# 28vdcEagle.net
KiCad netlist of a schematic drawn in EAGLE
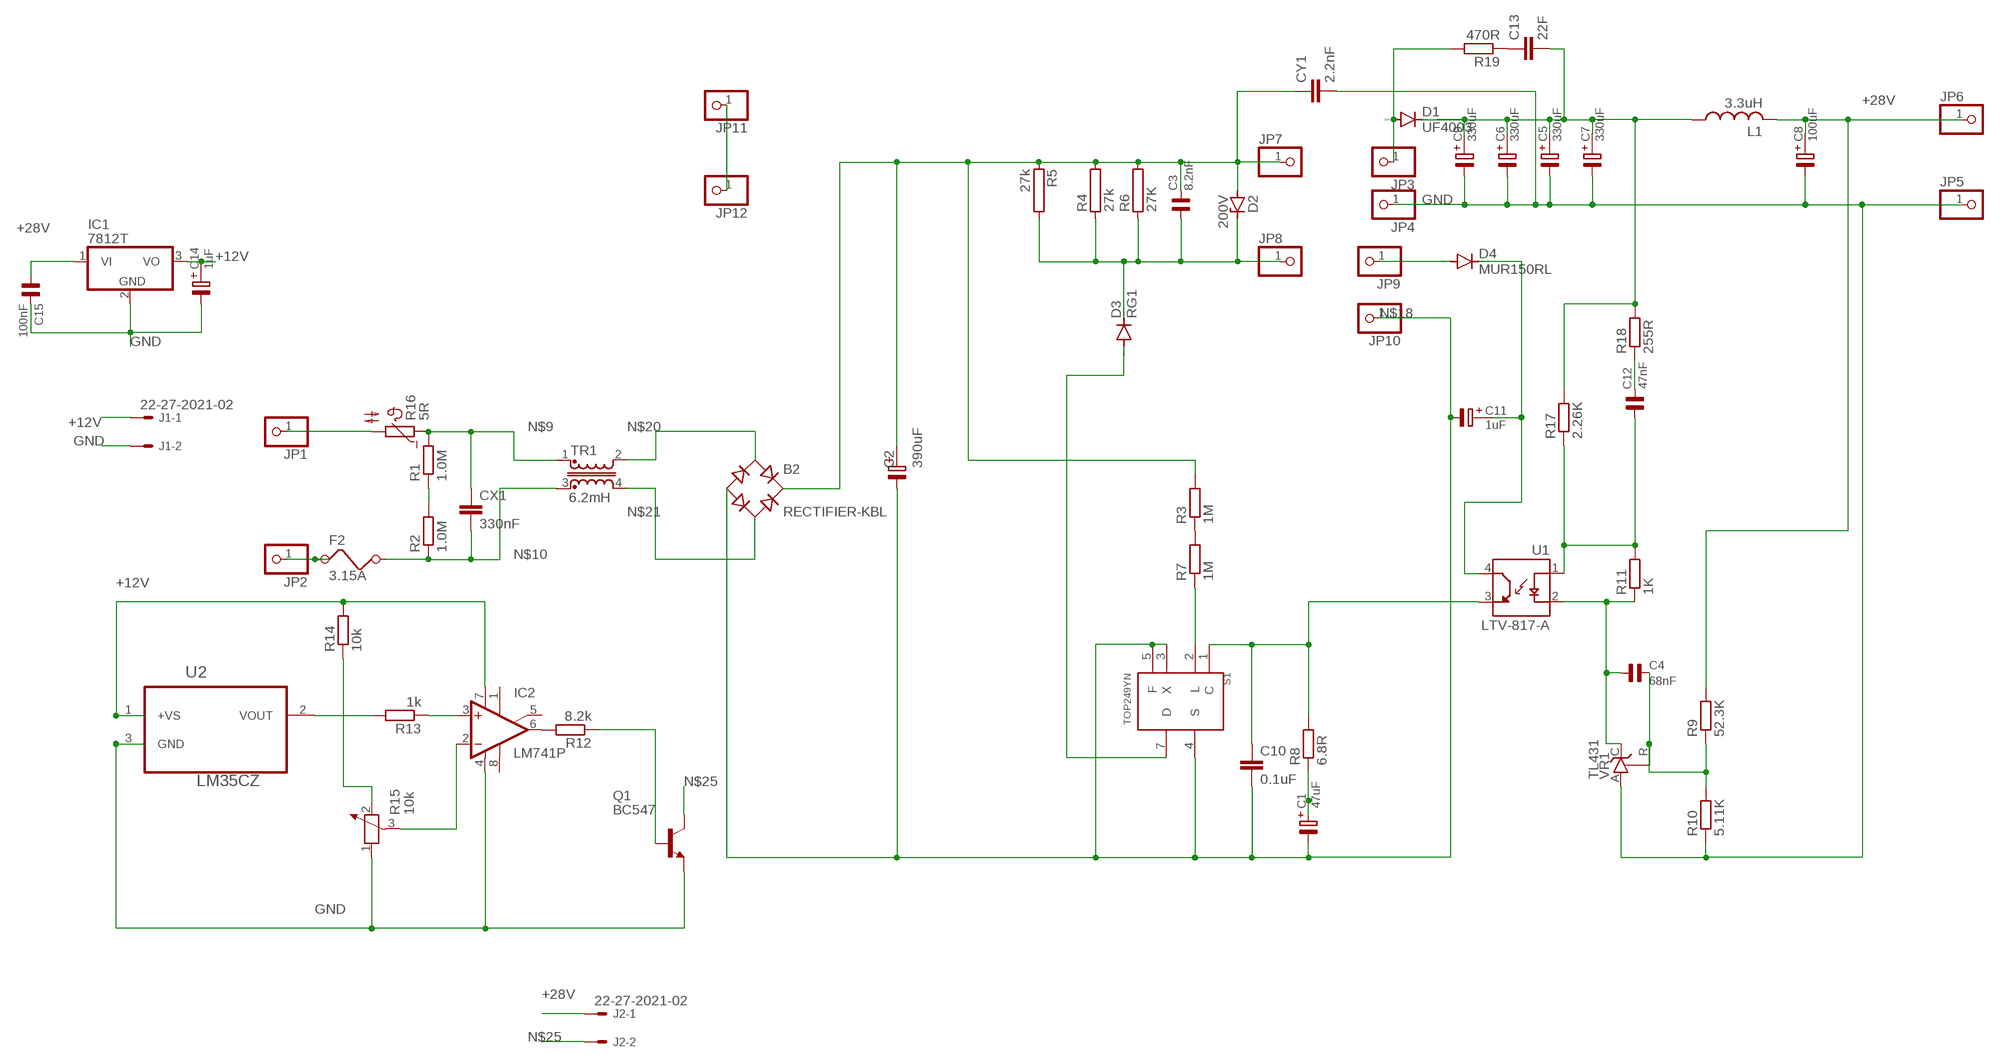
[diagram p0: schematic, sheet 1]

(export (version "E")
  (design (tool "Eeschema 10.0.6"))
  (components
    (comp (ref "B2")
      (value "RECTIFIER-KBL")
      (footprint "eagle-import:KBL")
      (libsource (lib "eagle-import") (part "RECTIFIER-KBL"))
    )
    (comp (ref "C1")
      (value "47uF")
      (footprint "eagle-import:E1,0-3")
      (libsource (lib "eagle-import") (part "E1,0-3"))
    )
    (comp (ref "C2")
      (value "390uF")
      (footprint "eagle-import:E3,5-10")
      (libsource (lib "eagle-import") (part "E3,5-10"))
    )
    (comp (ref "C3")
      (value "8.2nF")
      (footprint "eagle-import:C14,5")
      (libsource (lib "eagle-import") (part "C14,5"))
    )
    (comp (ref "C4")
      (value "68nF")
      (footprint "eagle-import:C2,5")
      (libsource (lib "eagle-import") (part "C2,5"))
    )
    (comp (ref "C5")
      (value "330uF")
      (footprint "eagle-import:E2,0-5")
      (libsource (lib "eagle-import") (part "E2,0-5"))
    )
    (comp (ref "C6")
      (value "330uF")
      (footprint "eagle-import:E2,0-5")
      (libsource (lib "eagle-import") (part "E2,0-5"))
    )
    (comp (ref "C7")
      (value "330uF")
      (footprint "eagle-import:E2,0-5")
      (libsource (lib "eagle-import") (part "E2,0-5"))
    )
    (comp (ref "C8")
      (value "100uF")
      (footprint "eagle-import:E2,0-5")
      (libsource (lib "eagle-import") (part "E2,0-5"))
    )
    (comp (ref "C9")
      (value "330uF")
      (footprint "eagle-import:E2,0-5")
      (libsource (lib "eagle-import") (part "E2,0-5"))
    )
    (comp (ref "C10")
      (value "0.1uF")
      (footprint "eagle-import:C025-030X050")
      (libsource (lib "eagle-import") (part "C-EU025-030X050"))
    )
    (comp (ref "C11")
      (value "1uF")
      (footprint "eagle-import:E1,0-3")
      (libsource (lib "eagle-import") (part "E1,0-3"))
    )
    (comp (ref "C12")
      (value "47nF")
      (footprint "eagle-import:C2,5")
      (libsource (lib "eagle-import") (part "C2,5"))
    )
    (comp (ref "C13")
      (value "22F")
      (footprint "eagle-import:C025-030X050")
      (libsource (lib "eagle-import") (part "C-EU025-030X050"))
    )
    (comp (ref "C14")
      (value "1uF")
      (footprint "eagle-import:E1,0-3")
      (libsource (lib "eagle-import") (part "E1,0-3"))
    )
    (comp (ref "C15")
      (value "100nF")
      (footprint "eagle-import:C2,5")
      (libsource (lib "eagle-import") (part "C2,5"))
    )
    (comp (ref "CX1")
      (value "330nF")
      (footprint "eagle-import:XC15B10")
      (libsource (lib "eagle-import") (part "CXXC15B10"))
    )
    (comp (ref "CY1")
      (value "2.2nF")
      (footprint "eagle-import:YC7B5")
      (libsource (lib "eagle-import") (part "CYYC7B5"))
    )
    (comp (ref "D1")
      (value "UF4003")
      (footprint "eagle-import:DO41-10")
      (libsource (lib "eagle-import") (part "UF4003"))
    )
    (comp (ref "D2")
      (value "200V")
      (footprint "eagle-import:C1702-15")
      (libsource (lib "eagle-import") (part "ZENER-DIODEC1702-15"))
    )
    (comp (ref "D3")
      (value "RG1")
      (footprint "eagle-import:DO204-10")
      (libsource (lib "eagle-import") (part "RG1"))
    )
    (comp (ref "D4")
      (value "MUR150RL")
      (footprint "eagle-import:DO41-10")
      (libsource (lib "eagle-import") (part "MUR150RL"))
    )
    (comp (ref "F2")
      (value "3.15A")
      (footprint "eagle-import:FUSE")
      (libsource (lib "eagle-import") (part "FUSE"))
    )
    (comp (ref "IC1")
      (value "7812T")
      (footprint "eagle-import:TO220H")
      (libsource (lib "eagle-import") (part "78T12"))
    )
    (comp (ref "IC2")
      (value "LM741P")
      (footprint "eagle-import:DIL08")
      (libsource (lib "eagle-import") (part "741PLM"))
    )
    (comp (ref "J1")
      (value "22-27-2021-02")
      (footprint "eagle-import:6410-02")
      (fields (field (name "MF") "MOLEX"))
      (libsource (lib "eagle-import") (part "22-?-0227-2021"))
    )
    (comp (ref "J2")
      (value "22-27-2021-02")
      (footprint "eagle-import:6410-02")
      (fields (field (name "MF") "MOLEX"))
      (libsource (lib "eagle-import") (part "22-?-0227-2021"))
    )
    (comp (ref "JP1")
      (value "PINHD-1X1")
      (footprint "eagle-import:1X01")
      (libsource (lib "eagle-import") (part "PINHD-1X1"))
    )
    (comp (ref "JP2")
      (value "PINHD-1X1")
      (footprint "eagle-import:1X01")
      (libsource (lib "eagle-import") (part "PINHD-1X1"))
    )
    (comp (ref "JP3")
      (value "PINHD-1X1")
      (footprint "eagle-import:1X01")
      (libsource (lib "eagle-import") (part "PINHD-1X1"))
    )
    (comp (ref "JP4")
      (value "PINHD-1X1")
      (footprint "eagle-import:1X01")
      (libsource (lib "eagle-import") (part "PINHD-1X1"))
    )
    (comp (ref "JP5")
      (value "PINHD-1X1")
      (footprint "eagle-import:1X01")
      (libsource (lib "eagle-import") (part "PINHD-1X1"))
    )
    (comp (ref "JP6")
      (value "PINHD-1X1")
      (footprint "eagle-import:1X01")
      (libsource (lib "eagle-import") (part "PINHD-1X1"))
    )
    (comp (ref "JP7")
      (value "PINHD-1X1")
      (footprint "eagle-import:1X01")
      (libsource (lib "eagle-import") (part "PINHD-1X1"))
    )
    (comp (ref "JP8")
      (value "PINHD-1X1")
      (footprint "eagle-import:1X01")
      (libsource (lib "eagle-import") (part "PINHD-1X1"))
    )
    (comp (ref "JP9")
      (value "PINHD-1X1")
      (footprint "eagle-import:1X01")
      (libsource (lib "eagle-import") (part "PINHD-1X1"))
    )
    (comp (ref "JP10")
      (value "PINHD-1X1")
      (footprint "eagle-import:1X01")
      (libsource (lib "eagle-import") (part "PINHD-1X1"))
    )
    (comp (ref "JP11")
      (value "PINHD-1X1")
      (footprint "eagle-import:1X01")
      (libsource (lib "eagle-import") (part "PINHD-1X1"))
    )
    (comp (ref "JP12")
      (value "PINHD-1X1")
      (footprint "eagle-import:1X01")
      (libsource (lib "eagle-import") (part "PINHD-1X1"))
    )
    (comp (ref "L1")
      (value "3.3uH")
      (footprint "eagle-import:0207_10")
      (libsource (lib "eagle-import") (part "L-US0207/10"))
    )
    (comp (ref "Q1")
      (value "BC547")
      (footprint "eagle-import:TO92")
      (libsource (lib "eagle-import") (part "BC547"))
    )
    (comp (ref "R1")
      (value "1.0M")
      (footprint "eagle-import:0207_10")
      (libsource (lib "eagle-import") (part "R-EU_0207/10"))
    )
    (comp (ref "R2")
      (value "1.0M")
      (footprint "eagle-import:0207_10")
      (libsource (lib "eagle-import") (part "R-EU_0207/10"))
    )
    (comp (ref "R3")
      (value "1M")
      (footprint "eagle-import:0207_10")
      (libsource (lib "eagle-import") (part "R-EU_0207/10"))
    )
    (comp (ref "R4")
      (value "27k")
      (footprint "eagle-import:KP290")
      (libsource (lib "eagle-import") (part "RKP290"))
    )
    (comp (ref "R5")
      (value "27k")
      (footprint "eagle-import:KP290")
      (libsource (lib "eagle-import") (part "RKP290"))
    )
    (comp (ref "R6")
      (value "27K")
      (footprint "eagle-import:KP290")
      (libsource (lib "eagle-import") (part "RKP290"))
    )
    (comp (ref "R7")
      (value "1M")
      (footprint "eagle-import:0207_10")
      (libsource (lib "eagle-import") (part "R-EU_0207/10"))
    )
    (comp (ref "R8")
      (value "6.8R")
      (footprint "eagle-import:0207_10")
      (libsource (lib "eagle-import") (part "R-EU_0207/10"))
    )
    (comp (ref "R9")
      (value "52.3K")
      (footprint "eagle-import:0207_10")
      (libsource (lib "eagle-import") (part "R-EU_0207/10"))
    )
    (comp (ref "R10")
      (value "5.11K")
      (footprint "eagle-import:0207_10")
      (libsource (lib "eagle-import") (part "R-EU_0207/10"))
    )
    (comp (ref "R11")
      (value "1K")
      (footprint "eagle-import:0207_10")
      (libsource (lib "eagle-import") (part "R-EU_0207/10"))
    )
    (comp (ref "R12")
      (value "8.2k")
      (footprint "eagle-import:0207_10")
      (libsource (lib "eagle-import") (part "R-EU_0207/10"))
    )
    (comp (ref "R13")
      (value "1k")
      (footprint "eagle-import:0207_10")
      (libsource (lib "eagle-import") (part "R-EU_0207/10"))
    )
    (comp (ref "R14")
      (value "10k")
      (footprint "eagle-import:0207_10")
      (libsource (lib "eagle-import") (part "R-EU_0207/10"))
    )
    (comp (ref "R15")
      (value "10k")
      (footprint "eagle-import:PT-10")
      (libsource (lib "eagle-import") (part "POTENTIOMETER_PT-10"))
    )
    (comp (ref "R16")
      (value "5R")
      (footprint "eagle-import:B57164")
      (fields (field (name "MPN") "B57164K474K52"))
      (libsource (lib "eagle-import") (part "B57164"))
    )
    (comp (ref "R17")
      (value "2.26K")
      (footprint "eagle-import:0207_10")
      (libsource (lib "eagle-import") (part "R-EU_0207/10"))
    )
    (comp (ref "R18")
      (value "255R")
      (footprint "eagle-import:0207_10")
      (libsource (lib "eagle-import") (part "R-EU_0207/10"))
    )
    (comp (ref "R19")
      (value "470R")
      (footprint "eagle-import:0207_10")
      (libsource (lib "eagle-import") (part "R-EU_0207/10"))
    )
    (comp (ref "S1")
      (value "TOP249YN")
      (footprint "eagle-import:TO127P470X1029X2061-7P")
      (fields (field (name "DIGI-KEY_PART_NUMBER") "596-1080-5-ND") (field (name "MF") "Power Integrations"))
      (libsource (lib "eagle-import") (part "TOP249YN"))
    )
    (comp (ref "TR1")
      (value "6.2mH")
      (footprint "eagle-import:U15")
      (libsource (lib "eagle-import") (part "U15-TRANSFORMER"))
    )
    (comp (ref "U1")
      (value "LTV-817-A")
      (footprint "eagle-import:DIP762W50P254L510H500Q4")
      (fields (field (name "MF") "Lite-On Inc."))
      (libsource (lib "eagle-import") (part "LTV-817-A"))
    )
    (comp (ref "U2")
      (value "LM35CZ")
      (footprint "eagle-import:TO127P254X495-3P")
      (fields (field (name "MF") "Texas Instruments"))
      (libsource (lib "eagle-import") (part "LM35CZ"))
    )
    (comp (ref "VR1")
      (value "TL431")
      (footprint "eagle-import:TO92-CLP")
      (libsource (lib "eagle-import") (part "TL431CLP"))
    )
  )
  (nets
    (net (code "1") (name "/+12V") (class "Default")
      (node (ref "C14") (pin "+") (pinfunction "+_+") (pintype "passive"))
      (node (ref "IC1") (pin "3") (pinfunction "VO_3") (pintype "passive"))
      (node (ref "IC2") (pin "7") (pinfunction "V+_7") (pintype "power_in"))
      (node (ref "J1") (pin "1") (pinfunction "S_1") (pintype "passive"))
      (node (ref "R14") (pin "2") (pinfunction "2_2") (pintype "passive"))
      (node (ref "U2") (pin "1") (pinfunction "+VS_1") (pintype "power_in"))
    )
    (net (code "2") (name "/+28V") (class "Default")
      (node (ref "C15") (pin "1") (pinfunction "1_1") (pintype "passive"))
      (node (ref "C8") (pin "+") (pinfunction "+_+") (pintype "passive"))
      (node (ref "IC1") (pin "1") (pinfunction "VI_1") (pintype "input"))
      (node (ref "J2") (pin "1") (pinfunction "S_1") (pintype "passive"))
      (node (ref "JP6") (pin "1") (pinfunction "1_1") (pintype "passive"))
      (node (ref "L1") (pin "2") (pinfunction "2_2") (pintype "passive"))
      (node (ref "R9") (pin "2") (pinfunction "2_2") (pintype "passive"))
    )
    (net (code "3") (name "/GND") (class "Default")
      (node (ref "C14") (pin "-") (pinfunction "-_-") (pintype "passive"))
      (node (ref "C15") (pin "2") (pinfunction "2_2") (pintype "passive"))
      (node (ref "C5") (pin "-") (pinfunction "-_-") (pintype "passive"))
      (node (ref "C6") (pin "-") (pinfunction "-_-") (pintype "passive"))
      (node (ref "C7") (pin "-") (pinfunction "-_-") (pintype "passive"))
      (node (ref "C8") (pin "-") (pinfunction "-_-") (pintype "passive"))
      (node (ref "C9") (pin "-") (pinfunction "-_-") (pintype "passive"))
      (node (ref "CY1") (pin "2") (pinfunction "2_2") (pintype "passive"))
      (node (ref "IC1") (pin "2") (pinfunction "GND_2") (pintype "passive"))
      (node (ref "IC2") (pin "4") (pinfunction "V-_4") (pintype "power_in"))
      (node (ref "J1") (pin "2") (pinfunction "S_2") (pintype "passive"))
      (node (ref "JP4") (pin "1") (pinfunction "1_1") (pintype "passive"))
      (node (ref "JP5") (pin "1") (pinfunction "1_1") (pintype "passive"))
      (node (ref "Q1") (pin "1") (pinfunction "E_1") (pintype "passive"))
      (node (ref "R10") (pin "1") (pinfunction "1_1") (pintype "passive"))
      (node (ref "R15") (pin "1") (pinfunction "1_1") (pintype "passive"))
      (node (ref "U2") (pin "3") (pinfunction "GND_3") (pintype "passive"))
      (node (ref "VR1") (pin "A") (pinfunction "A_A") (pintype "passive"))
    )
    (net (code "4") (name "/N$9") (class "Default")
      (node (ref "CX1") (pin "1") (pinfunction "1_1") (pintype "passive"))
      (node (ref "R1") (pin "2") (pinfunction "2_2") (pintype "passive"))
      (node (ref "R16") (pin "1") (pinfunction "1_1") (pintype "passive"))
      (node (ref "TR1") (pin "1") (pinfunction "1_1") (pintype "passive"))
    )
    (net (code "5") (name "/N$10") (class "Default")
      (node (ref "CX1") (pin "2") (pinfunction "2_2") (pintype "passive"))
      (node (ref "F2") (pin "2") (pinfunction "2_2") (pintype "passive"))
      (node (ref "R2") (pin "1") (pinfunction "1_1") (pintype "passive"))
      (node (ref "TR1") (pin "3") (pinfunction "3_3") (pintype "passive"))
    )
    (net (code "6") (name "/N$18") (class "Default")
      (node (ref "B2") (pin "-") (pinfunction "-_-") (pintype "passive"))
      (node (ref "C1") (pin "-") (pinfunction "-_-") (pintype "passive"))
      (node (ref "C10") (pin "2") (pinfunction "2_2") (pintype "passive"))
      (node (ref "C11") (pin "-") (pinfunction "-_-") (pintype "passive"))
      (node (ref "C2") (pin "-") (pinfunction "-_-") (pintype "passive"))
      (node (ref "JP10") (pin "1") (pinfunction "1_1") (pintype "passive"))
      (node (ref "S1") (pin "3") (pinfunction "X_3") (pintype "input"))
      (node (ref "S1") (pin "4") (pinfunction "S_4") (pintype "output"))
      (node (ref "S1") (pin "5") (pinfunction "F_5") (pintype "input"))
    )
    (net (code "7") (name "/N$20") (class "Default")
      (node (ref "B2") (pin "AC1") (pinfunction "AC1_AC1") (pintype "passive"))
      (node (ref "TR1") (pin "2") (pinfunction "2_2") (pintype "passive"))
    )
    (net (code "8") (name "/N$21") (class "Default")
      (node (ref "B2") (pin "AC2") (pinfunction "AC2_AC2") (pintype "passive"))
      (node (ref "TR1") (pin "4") (pinfunction "4_4") (pintype "passive"))
    )
    (net (code "9") (name "/N$25") (class "Default")
      (node (ref "J2") (pin "2") (pinfunction "S_2") (pintype "passive"))
      (node (ref "Q1") (pin "3") (pinfunction "C_3") (pintype "passive"))
    )
    (net (code "10") (name "Net-(B2-Pad+)") (class "Default")
      (node (ref "B2") (pin "+") (pinfunction "+_+") (pintype "passive"))
      (node (ref "C2") (pin "+") (pinfunction "+_+") (pintype "passive"))
      (node (ref "C3") (pin "2") (pinfunction "2_2") (pintype "passive"))
      (node (ref "CY1") (pin "1") (pinfunction "1_1") (pintype "passive"))
      (node (ref "D2") (pin "A") (pinfunction "A_A") (pintype "passive"))
      (node (ref "JP7") (pin "1") (pinfunction "1_1") (pintype "passive"))
      (node (ref "R3") (pin "2") (pinfunction "2_2") (pintype "passive"))
      (node (ref "R4") (pin "2") (pinfunction "2_2") (pintype "passive"))
      (node (ref "R5") (pin "1") (pinfunction "1_1") (pintype "passive"))
      (node (ref "R6") (pin "2") (pinfunction "2_2") (pintype "passive"))
    )
    (net (code "11") (name "Net-(C1-Pad+)") (class "Default")
      (node (ref "C1") (pin "+") (pinfunction "+_+") (pintype "passive"))
      (node (ref "R8") (pin "1") (pinfunction "1_1") (pintype "passive"))
    )
    (net (code "12") (name "Net-(C3-Pad1)") (class "Default")
      (node (ref "C3") (pin "1") (pinfunction "1_1") (pintype "passive"))
      (node (ref "D2") (pin "C") (pinfunction "C_C") (pintype "passive"))
      (node (ref "D3") (pin "C") (pinfunction "C_C") (pintype "passive"))
      (node (ref "JP8") (pin "1") (pinfunction "1_1") (pintype "passive"))
      (node (ref "R4") (pin "1") (pinfunction "1_1") (pintype "passive"))
      (node (ref "R5") (pin "2") (pinfunction "2_2") (pintype "passive"))
      (node (ref "R6") (pin "1") (pinfunction "1_1") (pintype "passive"))
    )
    (net (code "13") (name "Net-(C4-Pad2)") (class "Default")
      (node (ref "C4") (pin "2") (pinfunction "2_2") (pintype "passive"))
      (node (ref "R10") (pin "2") (pinfunction "2_2") (pintype "passive"))
      (node (ref "R9") (pin "1") (pinfunction "1_1") (pintype "passive"))
      (node (ref "VR1") (pin "R") (pinfunction "R_R") (pintype "passive"))
    )
    (net (code "14") (name "Net-(C12-Pad2)") (class "Default")
      (node (ref "C12") (pin "2") (pinfunction "2_2") (pintype "passive"))
      (node (ref "R18") (pin "1") (pinfunction "1_1") (pintype "passive"))
    )
    (net (code "15") (name "Net-(C13-Pad1)") (class "Default")
      (node (ref "C13") (pin "1") (pinfunction "1_1") (pintype "passive"))
      (node (ref "R19") (pin "1") (pinfunction "1_1") (pintype "passive"))
    )
    (net (code "16") (name "Net-(C13-Pad2)") (class "Default")
      (node (ref "C13") (pin "2") (pinfunction "2_2") (pintype "passive"))
      (node (ref "C5") (pin "+") (pinfunction "+_+") (pintype "passive"))
      (node (ref "C6") (pin "+") (pinfunction "+_+") (pintype "passive"))
      (node (ref "C7") (pin "+") (pinfunction "+_+") (pintype "passive"))
      (node (ref "C9") (pin "+") (pinfunction "+_+") (pintype "passive"))
      (node (ref "D1") (pin "C") (pinfunction "C_C") (pintype "passive"))
      (node (ref "L1") (pin "1") (pinfunction "1_1") (pintype "passive"))
      (node (ref "R17") (pin "2") (pinfunction "2_2") (pintype "passive"))
      (node (ref "R18") (pin "2") (pinfunction "2_2") (pintype "passive"))
    )
    (net (code "17") (name "Net-(D1-PadA)") (class "Default")
      (node (ref "D1") (pin "A") (pinfunction "A_A") (pintype "passive"))
      (node (ref "JP3") (pin "1") (pinfunction "1_1") (pintype "passive"))
      (node (ref "R19") (pin "2") (pinfunction "2_2") (pintype "passive"))
    )
    (net (code "18") (name "Net-(D4-PadA)") (class "Default")
      (node (ref "D4") (pin "A") (pinfunction "A_A") (pintype "passive"))
      (node (ref "JP9") (pin "1") (pinfunction "1_1") (pintype "passive"))
    )
    (net (code "19") (name "Net-(F2-Pad1)") (class "Default")
      (node (ref "F2") (pin "1") (pinfunction "1_1") (pintype "passive"))
      (node (ref "JP2") (pin "1") (pinfunction "1_1") (pintype "passive"))
    )
    (net (code "20") (name "Net-(IC2-+IN)") (class "Default")
      (node (ref "IC2") (pin "3") (pinfunction "+IN_3") (pintype "input"))
      (node (ref "R13") (pin "1") (pinfunction "1_1") (pintype "passive"))
    )
    (net (code "21") (name "Net-(IC2--IN)") (class "Default")
      (node (ref "IC2") (pin "2") (pinfunction "-IN_2") (pintype "input"))
      (node (ref "R15") (pin "3") (pinfunction "3_3") (pintype "passive"))
    )
    (net (code "22") (name "Net-(IC2-OUT)") (class "Default")
      (node (ref "IC2") (pin "6") (pinfunction "OUT_6") (pintype "output"))
      (node (ref "R12") (pin "2") (pinfunction "2_2") (pintype "passive"))
    )
    (net (code "23") (name "Net-(JP1-Pad1)") (class "Default")
      (node (ref "JP1") (pin "1") (pinfunction "1_1") (pintype "passive"))
      (node (ref "R16") (pin "2") (pinfunction "2_2") (pintype "passive"))
    )
    (net (code "24") (name "Net-(JP11-Pad1)") (class "Default")
      (node (ref "JP11") (pin "1") (pinfunction "1_1") (pintype "passive"))
      (node (ref "JP12") (pin "1") (pinfunction "1_1") (pintype "passive"))
    )
    (net (code "25") (name "Net-(Q1-B)") (class "Default")
      (node (ref "Q1") (pin "2") (pinfunction "B_2") (pintype "passive"))
      (node (ref "R12") (pin "1") (pinfunction "1_1") (pintype "passive"))
    )
    (net (code "26") (name "Net-(R1-Pad1)") (class "Default")
      (node (ref "R1") (pin "1") (pinfunction "1_1") (pintype "passive"))
      (node (ref "R2") (pin "2") (pinfunction "2_2") (pintype "passive"))
    )
    (net (code "27") (name "Net-(R3-Pad1)") (class "Default")
      (node (ref "R3") (pin "1") (pinfunction "1_1") (pintype "passive"))
      (node (ref "R7") (pin "2") (pinfunction "2_2") (pintype "passive"))
    )
    (net (code "28") (name "Net-(R14-Pad1)") (class "Default")
      (node (ref "R14") (pin "1") (pinfunction "1_1") (pintype "passive"))
      (node (ref "R15") (pin "2") (pinfunction "2_2") (pintype "passive"))
    )
    (net (code "29") (name "Net-(S1-C)") (class "Default")
      (node (ref "C10") (pin "1") (pinfunction "1_1") (pintype "passive"))
      (node (ref "R8") (pin "2") (pinfunction "2_2") (pintype "passive"))
      (node (ref "S1") (pin "1") (pinfunction "C_1") (pintype "input"))
      (node (ref "U1") (pin "3") (pinfunction "ET_3") (pintype "passive"))
    )
    (net (code "30") (name "Net-(S1-D)") (class "Default")
      (node (ref "D3") (pin "A") (pinfunction "A_A") (pintype "passive"))
      (node (ref "S1") (pin "7") (pinfunction "D_7") (pintype "output"))
    )
    (net (code "31") (name "Net-(S1-L)") (class "Default")
      (node (ref "R7") (pin "1") (pinfunction "1_1") (pintype "passive"))
      (node (ref "S1") (pin "2") (pinfunction "L_2") (pintype "input"))
    )
    (net (code "32") (name "Net-(U1-A)") (class "Default")
      (node (ref "C12") (pin "1") (pinfunction "1_1") (pintype "passive"))
      (node (ref "R11") (pin "2") (pinfunction "2_2") (pintype "passive"))
      (node (ref "R17") (pin "1") (pinfunction "1_1") (pintype "passive"))
      (node (ref "U1") (pin "1") (pinfunction "A_1") (pintype "passive"))
    )
    (net (code "33") (name "Net-(U1-C)") (class "Default")
      (node (ref "C4") (pin "1") (pinfunction "1_1") (pintype "passive"))
      (node (ref "R11") (pin "1") (pinfunction "1_1") (pintype "passive"))
      (node (ref "U1") (pin "2") (pinfunction "C_2") (pintype "passive"))
      (node (ref "VR1") (pin "C") (pinfunction "C_C") (pintype "passive"))
    )
    (net (code "34") (name "Net-(U1-CT)") (class "Default")
      (node (ref "C11") (pin "+") (pinfunction "+_+") (pintype "passive"))
      (node (ref "D4") (pin "C") (pinfunction "C_C") (pintype "passive"))
      (node (ref "U1") (pin "4") (pinfunction "CT_4") (pintype "passive"))
    )
    (net (code "35") (name "Net-(U2-VOUT)") (class "Default")
      (node (ref "R13") (pin "2") (pinfunction "2_2") (pintype "passive"))
      (node (ref "U2") (pin "2") (pinfunction "VOUT_2") (pintype "output"))
    )
    (net (code "36") (name "unconnected-(IC2-ON1-Pad1)") (class "Default")
      (node (ref "IC2") (pin "1") (pinfunction "ON1_1") (pintype "passive"))
    )
    (net (code "37") (name "unconnected-(IC2-ON2-Pad5)") (class "Default")
      (node (ref "IC2") (pin "5") (pinfunction "ON2_5") (pintype "passive"))
    )
    (net (code "38") (name "unconnected-(IC2-OPT-Pad8)") (class "Default")
      (node (ref "IC2") (pin "8") (pinfunction "OPT_8") (pintype "passive"))
    )
  )
)
